# 30_SOC.net
KiCad netlist of a schematic drawn in Altium Designer
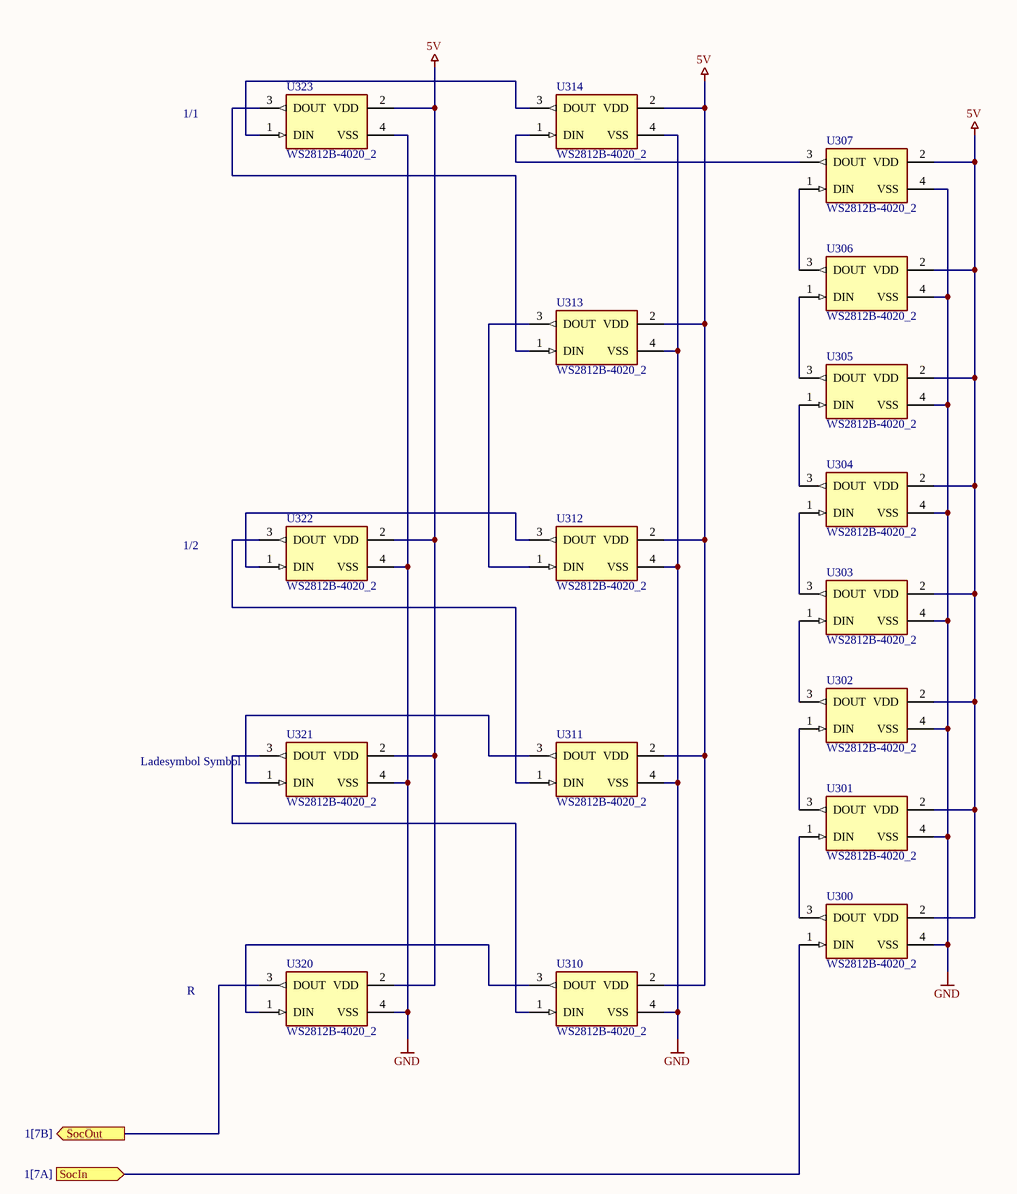
[diagram p0: 30_SOC.SchDoc]

(export (version "E")
  (design (tool "Eeschema 10.0.6"))
  (components
    (comp (ref "U300")
      (value "WS2812B-4020_2")
      (footprint "LED_WS2812B-4020")
      (description "12mA RGB SMD,2x4mm Light Emitting Diodes")
      (fields (field (name "MP") "WS2812B-4020") (field (name "MF") "Worldsemi"))
      (libsource (lib "AltiumLib_MILUTIN") (part "WS2812B-4020_2"))
    )
    (comp (ref "U301")
      (value "WS2812B-4020_2")
      (footprint "LED_WS2812B-4020")
      (description "12mA RGB SMD,2x4mm Light Emitting Diodes")
      (fields (field (name "MP") "WS2812B-4020") (field (name "MF") "Worldsemi"))
      (libsource (lib "AltiumLib_MILUTIN") (part "WS2812B-4020_2"))
    )
    (comp (ref "U302")
      (value "WS2812B-4020_2")
      (footprint "LED_WS2812B-4020")
      (description "12mA RGB SMD,2x4mm Light Emitting Diodes")
      (fields (field (name "MP") "WS2812B-4020") (field (name "MF") "Worldsemi"))
      (libsource (lib "AltiumLib_MILUTIN") (part "WS2812B-4020_2"))
    )
    (comp (ref "U303")
      (value "WS2812B-4020_2")
      (footprint "LED_WS2812B-4020")
      (description "12mA RGB SMD,2x4mm Light Emitting Diodes")
      (fields (field (name "MP") "WS2812B-4020") (field (name "MF") "Worldsemi"))
      (libsource (lib "AltiumLib_MILUTIN") (part "WS2812B-4020_2"))
    )
    (comp (ref "U304")
      (value "WS2812B-4020_2")
      (footprint "LED_WS2812B-4020")
      (description "12mA RGB SMD,2x4mm Light Emitting Diodes")
      (fields (field (name "MP") "WS2812B-4020") (field (name "MF") "Worldsemi"))
      (libsource (lib "AltiumLib_MILUTIN") (part "WS2812B-4020_2"))
    )
    (comp (ref "U305")
      (value "WS2812B-4020_2")
      (footprint "LED_WS2812B-4020")
      (description "12mA RGB SMD,2x4mm Light Emitting Diodes")
      (fields (field (name "MP") "WS2812B-4020") (field (name "MF") "Worldsemi"))
      (libsource (lib "AltiumLib_MILUTIN") (part "WS2812B-4020_2"))
    )
    (comp (ref "U306")
      (value "WS2812B-4020_2")
      (footprint "LED_WS2812B-4020")
      (description "12mA RGB SMD,2x4mm Light Emitting Diodes")
      (fields (field (name "MP") "WS2812B-4020") (field (name "MF") "Worldsemi"))
      (libsource (lib "AltiumLib_MILUTIN") (part "WS2812B-4020_2"))
    )
    (comp (ref "U307")
      (value "WS2812B-4020_2")
      (footprint "LED_WS2812B-4020")
      (description "12mA RGB SMD,2x4mm Light Emitting Diodes")
      (fields (field (name "MP") "WS2812B-4020") (field (name "MF") "Worldsemi"))
      (libsource (lib "AltiumLib_MILUTIN") (part "WS2812B-4020_2"))
    )
    (comp (ref "U310")
      (value "WS2812B-4020_2")
      (footprint "LED_WS2812B-4020")
      (description "12mA RGB SMD,2x4mm Light Emitting Diodes")
      (fields (field (name "MP") "WS2812B-4020") (field (name "MF") "Worldsemi"))
      (libsource (lib "AltiumLib_MILUTIN") (part "WS2812B-4020_2"))
    )
    (comp (ref "U311")
      (value "WS2812B-4020_2")
      (footprint "LED_WS2812B-4020")
      (description "12mA RGB SMD,2x4mm Light Emitting Diodes")
      (fields (field (name "MP") "WS2812B-4020") (field (name "MF") "Worldsemi"))
      (libsource (lib "AltiumLib_MILUTIN") (part "WS2812B-4020_2"))
    )
    (comp (ref "U312")
      (value "WS2812B-4020_2")
      (footprint "LED_WS2812B-4020")
      (description "12mA RGB SMD,2x4mm Light Emitting Diodes")
      (fields (field (name "MP") "WS2812B-4020") (field (name "MF") "Worldsemi"))
      (libsource (lib "AltiumLib_MILUTIN") (part "WS2812B-4020_2"))
    )
    (comp (ref "U313")
      (value "WS2812B-4020_2")
      (footprint "LED_WS2812B-4020")
      (description "12mA RGB SMD,2x4mm Light Emitting Diodes")
      (fields (field (name "MP") "WS2812B-4020") (field (name "MF") "Worldsemi"))
      (libsource (lib "AltiumLib_MILUTIN") (part "WS2812B-4020_2"))
    )
    (comp (ref "U314")
      (value "WS2812B-4020_2")
      (footprint "LED_WS2812B-4020")
      (description "12mA RGB SMD,2x4mm Light Emitting Diodes")
      (fields (field (name "MP") "WS2812B-4020") (field (name "MF") "Worldsemi"))
      (libsource (lib "AltiumLib_MILUTIN") (part "WS2812B-4020_2"))
    )
    (comp (ref "U320")
      (value "WS2812B-4020_2")
      (footprint "LED_WS2812B-4020")
      (description "12mA RGB SMD,2x4mm Light Emitting Diodes")
      (fields (field (name "MP") "WS2812B-4020") (field (name "MF") "Worldsemi"))
      (libsource (lib "AltiumLib_MILUTIN") (part "WS2812B-4020_2"))
    )
    (comp (ref "U321")
      (value "WS2812B-4020_2")
      (footprint "LED_WS2812B-4020")
      (description "12mA RGB SMD,2x4mm Light Emitting Diodes")
      (fields (field (name "MP") "WS2812B-4020") (field (name "MF") "Worldsemi"))
      (libsource (lib "AltiumLib_MILUTIN") (part "WS2812B-4020_2"))
    )
    (comp (ref "U322")
      (value "WS2812B-4020_2")
      (footprint "LED_WS2812B-4020")
      (description "12mA RGB SMD,2x4mm Light Emitting Diodes")
      (fields (field (name "MP") "WS2812B-4020") (field (name "MF") "Worldsemi"))
      (libsource (lib "AltiumLib_MILUTIN") (part "WS2812B-4020_2"))
    )
    (comp (ref "U323")
      (value "WS2812B-4020_2")
      (footprint "LED_WS2812B-4020")
      (description "12mA RGB SMD,2x4mm Light Emitting Diodes")
      (fields (field (name "MP") "WS2812B-4020") (field (name "MF") "Worldsemi"))
      (libsource (lib "AltiumLib_MILUTIN") (part "WS2812B-4020_2"))
    )
  )
  (nets
    (net (code "1") (name "/SocIn") (class "Default")
      (node (ref "U300") (pin "1") (pinfunction "DIN_1") (pintype "input"))
    )
    (net (code "2") (name "/SocOut") (class "Default")
      (node (ref "U320") (pin "3") (pinfunction "DOUT_3") (pintype "output"))
    )
    (net (code "3") (name "5V") (class "Default")
      (node (ref "U300") (pin "2") (pinfunction "VDD_2") (pintype "power_in"))
      (node (ref "U301") (pin "2") (pinfunction "VDD_2") (pintype "power_in"))
      (node (ref "U302") (pin "2") (pinfunction "VDD_2") (pintype "power_in"))
      (node (ref "U303") (pin "2") (pinfunction "VDD_2") (pintype "power_in"))
      (node (ref "U304") (pin "2") (pinfunction "VDD_2") (pintype "power_in"))
      (node (ref "U305") (pin "2") (pinfunction "VDD_2") (pintype "power_in"))
      (node (ref "U306") (pin "2") (pinfunction "VDD_2") (pintype "power_in"))
      (node (ref "U307") (pin "2") (pinfunction "VDD_2") (pintype "power_in"))
      (node (ref "U310") (pin "2") (pinfunction "VDD_2") (pintype "power_in"))
      (node (ref "U311") (pin "2") (pinfunction "VDD_2") (pintype "power_in"))
      (node (ref "U312") (pin "2") (pinfunction "VDD_2") (pintype "power_in"))
      (node (ref "U313") (pin "2") (pinfunction "VDD_2") (pintype "power_in"))
      (node (ref "U314") (pin "2") (pinfunction "VDD_2") (pintype "power_in"))
      (node (ref "U320") (pin "2") (pinfunction "VDD_2") (pintype "power_in"))
      (node (ref "U321") (pin "2") (pinfunction "VDD_2") (pintype "power_in"))
      (node (ref "U322") (pin "2") (pinfunction "VDD_2") (pintype "power_in"))
      (node (ref "U323") (pin "2") (pinfunction "VDD_2") (pintype "power_in"))
    )
    (net (code "4") (name "GND") (class "Default")
      (node (ref "U300") (pin "4") (pinfunction "VSS_4") (pintype "power_in"))
      (node (ref "U301") (pin "4") (pinfunction "VSS_4") (pintype "power_in"))
      (node (ref "U302") (pin "4") (pinfunction "VSS_4") (pintype "power_in"))
      (node (ref "U303") (pin "4") (pinfunction "VSS_4") (pintype "power_in"))
      (node (ref "U304") (pin "4") (pinfunction "VSS_4") (pintype "power_in"))
      (node (ref "U305") (pin "4") (pinfunction "VSS_4") (pintype "power_in"))
      (node (ref "U306") (pin "4") (pinfunction "VSS_4") (pintype "power_in"))
      (node (ref "U307") (pin "4") (pinfunction "VSS_4") (pintype "power_in"))
      (node (ref "U310") (pin "4") (pinfunction "VSS_4") (pintype "power_in"))
      (node (ref "U311") (pin "4") (pinfunction "VSS_4") (pintype "power_in"))
      (node (ref "U312") (pin "4") (pinfunction "VSS_4") (pintype "power_in"))
      (node (ref "U313") (pin "4") (pinfunction "VSS_4") (pintype "power_in"))
      (node (ref "U314") (pin "4") (pinfunction "VSS_4") (pintype "power_in"))
      (node (ref "U320") (pin "4") (pinfunction "VSS_4") (pintype "power_in"))
      (node (ref "U321") (pin "4") (pinfunction "VSS_4") (pintype "power_in"))
      (node (ref "U322") (pin "4") (pinfunction "VSS_4") (pintype "power_in"))
      (node (ref "U323") (pin "4") (pinfunction "VSS_4") (pintype "power_in"))
    )
    (net (code "5") (name "Net-(U300-DOUT)") (class "Default")
      (node (ref "U300") (pin "3") (pinfunction "DOUT_3") (pintype "output"))
      (node (ref "U301") (pin "1") (pinfunction "DIN_1") (pintype "input"))
    )
    (net (code "6") (name "Net-(U301-DOUT)") (class "Default")
      (node (ref "U301") (pin "3") (pinfunction "DOUT_3") (pintype "output"))
      (node (ref "U302") (pin "1") (pinfunction "DIN_1") (pintype "input"))
    )
    (net (code "7") (name "Net-(U302-DOUT)") (class "Default")
      (node (ref "U302") (pin "3") (pinfunction "DOUT_3") (pintype "output"))
      (node (ref "U303") (pin "1") (pinfunction "DIN_1") (pintype "input"))
    )
    (net (code "8") (name "Net-(U303-DOUT)") (class "Default")
      (node (ref "U303") (pin "3") (pinfunction "DOUT_3") (pintype "output"))
      (node (ref "U304") (pin "1") (pinfunction "DIN_1") (pintype "input"))
    )
    (net (code "9") (name "Net-(U304-DOUT)") (class "Default")
      (node (ref "U304") (pin "3") (pinfunction "DOUT_3") (pintype "output"))
      (node (ref "U305") (pin "1") (pinfunction "DIN_1") (pintype "input"))
    )
    (net (code "10") (name "Net-(U305-DOUT)") (class "Default")
      (node (ref "U305") (pin "3") (pinfunction "DOUT_3") (pintype "output"))
      (node (ref "U306") (pin "1") (pinfunction "DIN_1") (pintype "input"))
    )
    (net (code "11") (name "Net-(U306-DOUT)") (class "Default")
      (node (ref "U306") (pin "3") (pinfunction "DOUT_3") (pintype "output"))
      (node (ref "U307") (pin "1") (pinfunction "DIN_1") (pintype "input"))
    )
    (net (code "12") (name "Net-(U307-DOUT)") (class "Default")
      (node (ref "U307") (pin "3") (pinfunction "DOUT_3") (pintype "output"))
      (node (ref "U314") (pin "1") (pinfunction "DIN_1") (pintype "input"))
    )
    (net (code "13") (name "Net-(U310-DIN)") (class "Default")
      (node (ref "U310") (pin "1") (pinfunction "DIN_1") (pintype "input"))
      (node (ref "U321") (pin "3") (pinfunction "DOUT_3") (pintype "output"))
    )
    (net (code "14") (name "Net-(U310-DOUT)") (class "Default")
      (node (ref "U310") (pin "3") (pinfunction "DOUT_3") (pintype "output"))
      (node (ref "U320") (pin "1") (pinfunction "DIN_1") (pintype "input"))
    )
    (net (code "15") (name "Net-(U311-DIN)") (class "Default")
      (node (ref "U311") (pin "1") (pinfunction "DIN_1") (pintype "input"))
      (node (ref "U322") (pin "3") (pinfunction "DOUT_3") (pintype "output"))
    )
    (net (code "16") (name "Net-(U311-DOUT)") (class "Default")
      (node (ref "U311") (pin "3") (pinfunction "DOUT_3") (pintype "output"))
      (node (ref "U321") (pin "1") (pinfunction "DIN_1") (pintype "input"))
    )
    (net (code "17") (name "Net-(U312-DIN)") (class "Default")
      (node (ref "U312") (pin "1") (pinfunction "DIN_1") (pintype "input"))
      (node (ref "U313") (pin "3") (pinfunction "DOUT_3") (pintype "output"))
    )
    (net (code "18") (name "Net-(U312-DOUT)") (class "Default")
      (node (ref "U312") (pin "3") (pinfunction "DOUT_3") (pintype "output"))
      (node (ref "U322") (pin "1") (pinfunction "DIN_1") (pintype "input"))
    )
    (net (code "19") (name "Net-(U313-DIN)") (class "Default")
      (node (ref "U313") (pin "1") (pinfunction "DIN_1") (pintype "input"))
      (node (ref "U323") (pin "3") (pinfunction "DOUT_3") (pintype "output"))
    )
    (net (code "20") (name "Net-(U314-DOUT)") (class "Default")
      (node (ref "U314") (pin "3") (pinfunction "DOUT_3") (pintype "output"))
      (node (ref "U323") (pin "1") (pinfunction "DIN_1") (pintype "input"))
    )
  )
)
